# adapter.net
KiCad netlist of a schematic drawn in EAGLE
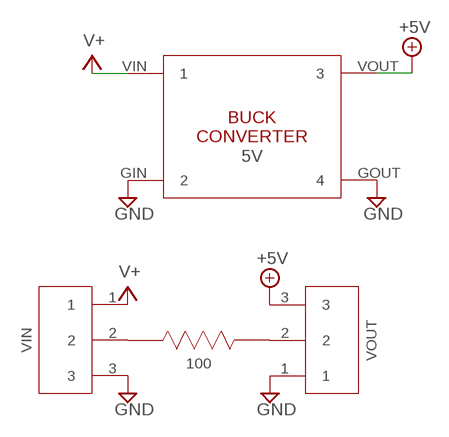
[diagram p0: schematic, sheet 1]

(export (version "E")
  (design (tool "Eeschema 10.0.6"))
  (components
    (comp (ref "U$1")
      (value "5V")
      (footprint "eagle-import:BUCK_CONVERTER")
      (libsource (lib "eagle-import") (part "BUCK_CONVERTER"))
    )
    (comp (ref "U$2")
      (value "100")
      (footprint "eagle-import:RESISTOR_THROUGHHOLE")
      (libsource (lib "eagle-import") (part "RESISTORTHROUGHHOLE"))
    )
    (comp (ref "VIN")
      (value "J3PIN")
      (footprint "eagle-import:J3PIN")
      (libsource (lib "eagle-import") (part "J3PIN"))
    )
    (comp (ref "VOUT")
      (value "J3PIN")
      (footprint "eagle-import:J3PIN")
      (libsource (lib "eagle-import") (part "J3PIN"))
    )
  )
  (nets
    (net (code "1") (name "+5V") (class "Default")
      (node (ref "U$1") (pin "VOUT") (pinfunction "3_VOUT") (pintype "bidirectional"))
      (node (ref "VOUT") (pin "3") (pinfunction "3_3") (pintype "bidirectional"))
    )
    (net (code "2") (name "GND") (class "Default")
      (node (ref "U$1") (pin "GIN") (pinfunction "2_GIN") (pintype "bidirectional"))
      (node (ref "U$1") (pin "GOUT") (pinfunction "4_GOUT") (pintype "bidirectional"))
      (node (ref "VIN") (pin "3") (pinfunction "3_3") (pintype "bidirectional"))
      (node (ref "VOUT") (pin "1") (pinfunction "1_1") (pintype "bidirectional"))
    )
    (net (code "3") (name "Net-(U$2-Pad1)") (class "Default")
      (node (ref "U$2") (pin "1") (pinfunction "1_1") (pintype "bidirectional"))
      (node (ref "VIN") (pin "2") (pinfunction "2_2") (pintype "bidirectional"))
    )
    (net (code "4") (name "Net-(U$2-Pad2)") (class "Default")
      (node (ref "U$2") (pin "2") (pinfunction "2_2") (pintype "bidirectional"))
      (node (ref "VOUT") (pin "2") (pinfunction "2_2") (pintype "bidirectional"))
    )
    (net (code "5") (name "V+") (class "Default")
      (node (ref "U$1") (pin "VIN") (pinfunction "1_VIN") (pintype "bidirectional"))
      (node (ref "VIN") (pin "1") (pinfunction "1_1") (pintype "bidirectional"))
    )
  )
)
